# MiniRacer_V2.net
KiCad netlist of a schematic drawn in Altium Designer
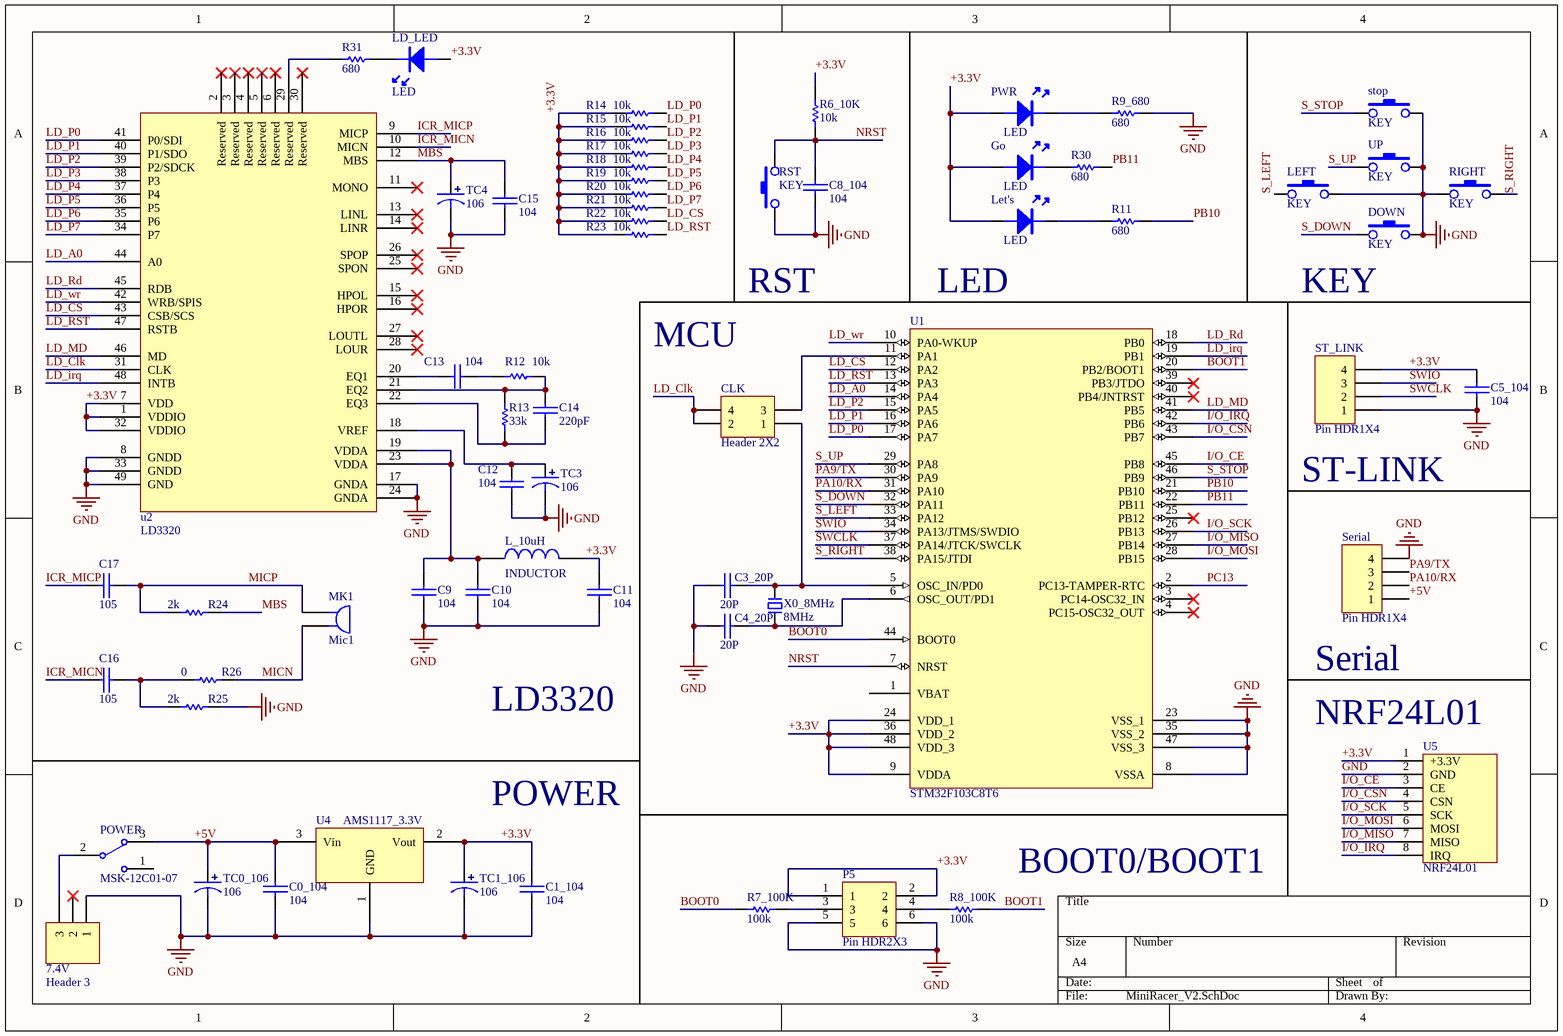
[diagram p0: MiniRacer_V2.SchDoc]

(export (version "E")
  (design (tool "Eeschema 10.0.6"))
  (components
    (comp (ref "7.4V")
      (value "Header 3")
      (footprint "HDR1X3")
      (description "Header, 3-Pin")
      (fields (field (name "PUBLISHER") "Altium Limited"))
      (libsource (lib "Miscellaneous Connectors") (part "Header 3"))
    )
    (comp (ref "C0_104")
      (value "104")
      (footprint "0603C")
      (description "无极性电容")
      (libsource (lib "电容") (part "CAP"))
    )
    (comp (ref "C1_104")
      (value "104")
      (footprint "0603C")
      (description "无极性电容")
      (libsource (lib "电容") (part "CAP"))
    )
    (comp (ref "C3_20P")
      (value "20P")
      (footprint "0603C")
      (description "无极性电容")
      (libsource (lib "电容") (part "CAP"))
    )
    (comp (ref "C4_20P")
      (value "20P")
      (footprint "0603C")
      (description "无极性电容")
      (libsource (lib "电容") (part "CAP"))
    )
    (comp (ref "C5_104")
      (value "104")
      (footprint "0603C")
      (description "无极性电容")
      (libsource (lib "电容") (part "CAP"))
    )
    (comp (ref "C8_104")
      (value "104")
      (footprint "0603C")
      (description "无极性电容")
      (libsource (lib "电容") (part "CAP"))
    )
    (comp (ref "C9")
      (value "104")
      (footprint "0603C")
      (description "无极性电容")
      (libsource (lib "电容") (part "CAP"))
    )
    (comp (ref "C10")
      (value "104")
      (footprint "0603C")
      (description "无极性电容")
      (libsource (lib "电容") (part "CAP"))
    )
    (comp (ref "C11")
      (value "104")
      (footprint "0603C")
      (description "无极性电容")
      (libsource (lib "电容") (part "CAP"))
    )
    (comp (ref "C12")
      (value "104")
      (footprint "0603C")
      (description "无极性电容")
      (libsource (lib "电容") (part "CAP"))
    )
    (comp (ref "C13")
      (value "104")
      (footprint "0603C")
      (description "无极性电容")
      (libsource (lib "电容") (part "CAP"))
    )
    (comp (ref "C14")
      (value "220pF")
      (footprint "0603C")
      (description "无极性电容")
      (libsource (lib "电容") (part "CAP"))
    )
    (comp (ref "C15")
      (value "104")
      (footprint "0603C")
      (description "无极性电容")
      (libsource (lib "电容") (part "CAP"))
    )
    (comp (ref "C16")
      (value "105")
      (footprint "0603C")
      (description "无极性电容")
      (libsource (lib "电容") (part "CAP"))
    )
    (comp (ref "C17")
      (value "105")
      (footprint "0603C")
      (description "无极性电容")
      (libsource (lib "电容") (part "CAP"))
    )
    (comp (ref "CLK")
      (value "Header 2X2")
      (footprint "HDR2X2")
      (description "Header, 2-Pin, Dual row")
      (fields (field (name "PUBLISHER") "Altium Limited"))
      (libsource (lib "Miscellaneous Connectors") (part "Header 2X2"))
    )
    (comp (ref "DOWN") (value "KEY") (footprint "DIP-3X6X4.3") (libsource (lib "轻触开关") (part "KEY")))
    (comp (ref "Go") (value "LED") (footprint "LED-0603Y") (libsource (lib "LED") (part "LED")))
    (comp (ref "LD_LED") (value "LED") (footprint "LED-0603Y") (libsource (lib "LED") (part "LED")))
    (comp (ref "LEFT") (value "KEY") (footprint "DIP-3X6X4.3") (libsource (lib "轻触开关") (part "KEY")))
    (comp (ref "Let's") (value "LED") (footprint "LED-0603Y") (libsource (lib "LED") (part "LED")))
    (comp (ref "L_10uH") (value "INDUCTOR") (footprint "0603L") (libsource (lib "电感") (part "INDUCTOR")))
    (comp (ref "MK1")
      (value "Mic1")
      (footprint "PIN2")
      (description "Microphone")
      (fields (field (name "PUBLISHER") "Altium Limited"))
      (libsource (lib "Miscellaneous Devices") (part "Mic1"))
    )
    (comp (ref "P5")
      (value "Pin HDR2X3")
      (footprint "Pin HDR2X3/2.54mm-S")
      (libsource (lib "排针") (part "Pin HDR2X3"))
    )
    (comp (ref "POWER")
      (value "MSK-12C01-07")
      (footprint "MSK-12C01-07")
      (libsource (lib "电源开关") (part "MSK-12C01-07"))
    )
    (comp (ref "PWR") (value "LED") (footprint "LED-0603Y") (libsource (lib "LED") (part "LED")))
    (comp (ref "R6_10K") (value "10k") (footprint "0603R") (libsource (lib "电阻") (part "RES")))
    (comp (ref "R7_100K") (value "100k") (footprint "0603R") (libsource (lib "电阻") (part "RES")))
    (comp (ref "R8_100K") (value "100k") (footprint "0603R") (libsource (lib "电阻") (part "RES")))
    (comp (ref "R9_680") (value "680") (footprint "0603R") (libsource (lib "电阻") (part "RES")))
    (comp (ref "R11") (value "680") (footprint "0603R") (libsource (lib "电阻") (part "RES")))
    (comp (ref "R12") (value "10k") (footprint "0603R") (libsource (lib "电阻") (part "RES")))
    (comp (ref "R13") (value "33k") (footprint "0603R") (libsource (lib "电阻") (part "RES")))
    (comp (ref "R14") (value "10k") (footprint "0603R") (libsource (lib "电阻") (part "RES")))
    (comp (ref "R15") (value "10k") (footprint "0603R") (libsource (lib "电阻") (part "RES")))
    (comp (ref "R16") (value "10k") (footprint "0603R") (libsource (lib "电阻") (part "RES")))
    (comp (ref "R17") (value "10k") (footprint "0603R") (libsource (lib "电阻") (part "RES")))
    (comp (ref "R18") (value "10k") (footprint "0603R") (libsource (lib "电阻") (part "RES")))
    (comp (ref "R19") (value "10k") (footprint "0603R") (libsource (lib "电阻") (part "RES")))
    (comp (ref "R20") (value "10k") (footprint "0603R") (libsource (lib "电阻") (part "RES")))
    (comp (ref "R21") (value "10k") (footprint "0603R") (libsource (lib "电阻") (part "RES")))
    (comp (ref "R22") (value "10k") (footprint "0603R") (libsource (lib "电阻") (part "RES")))
    (comp (ref "R23") (value "10k") (footprint "0603R") (libsource (lib "电阻") (part "RES")))
    (comp (ref "R24") (value "2k") (footprint "0603R") (libsource (lib "电阻") (part "RES")))
    (comp (ref "R25") (value "2k") (footprint "0603R") (libsource (lib "电阻") (part "RES")))
    (comp (ref "R26") (value "0") (footprint "0603R") (libsource (lib "电阻") (part "RES")))
    (comp (ref "R30") (value "680") (footprint "0603R") (libsource (lib "电阻") (part "RES")))
    (comp (ref "R31") (value "680") (footprint "0603R") (libsource (lib "电阻") (part "RES")))
    (comp (ref "RIGHT") (value "KEY") (footprint "DIP-3X6X4.3") (libsource (lib "轻触开关") (part "KEY")))
    (comp (ref "RST") (value "KEY") (footprint "SMD-3X6X2.5") (libsource (lib "轻触开关") (part "KEY")))
    (comp (ref "Serial")
      (value "Pin HDR1X4")
      (footprint "HDR1X4")
      (description "Header, 4-Pin")
      (fields (field (name "PUBLISHER") "Altium Limited"))
      (libsource (lib "Miscellaneous Connectors") (part "Header 4"))
    )
    (comp (ref "stop") (value "KEY") (footprint "DIP-3X6X4.3") (libsource (lib "轻触开关") (part "KEY")))
    (comp (ref "ST_LINK")
      (value "Pin HDR1X4")
      (footprint "HDR1X4")
      (description "Header, 4-Pin")
      (fields (field (name "PUBLISHER") "Altium Limited"))
      (libsource (lib "Miscellaneous Connectors") (part "Header 4"))
    )
    (comp (ref "TC0_106")
      (value "106")
      (footprint "TAJ-A/3216")
      (description "钽电容")
      (libsource (lib "电容") (part "TCAP"))
    )
    (comp (ref "TC1_106")
      (value "106")
      (footprint "TAJ-A/3216")
      (description "钽电容")
      (libsource (lib "电容") (part "TCAP"))
    )
    (comp (ref "TC3")
      (value "106")
      (footprint "TAJ-A/3216")
      (description "钽电容")
      (libsource (lib "电容") (part "TCAP"))
    )
    (comp (ref "TC4")
      (value "106")
      (footprint "TAJ-A/3216")
      (description "钽电容")
      (libsource (lib "电容") (part "TCAP"))
    )
    (comp (ref "U1")
      (value "STM32F103C8T6")
      (footprint "LQFP48 7X7")
      (libsource (lib "STM32系列") (part "STM32F103C8T6"))
    )
    (comp (ref "u2")
      (value "LD3320")
      (footprint "QFN50P700X700-48VAN")
      (libsource (lib "未分类IC") (part "LD3320"))
    )
    (comp (ref "U4")
      (value "AMS1117_3.3V")
      (footprint "SOT223")
      (description "三端稳压芯片")
      (libsource (lib "电源芯片") (part "AMS1117"))
    )
    (comp (ref "U5") (value "NRF24L01") (footprint "NRF24L01") (libsource (lib "未分类IC") (part "NRF24L01")))
    (comp (ref "UP") (value "KEY") (footprint "DIP-3X6X4.3") (libsource (lib "轻触开关") (part "KEY")))
    (comp (ref "X0_8MHz")
      (value "8MHz")
      (footprint "OSC 5032-2P")
      (description "2脚无源脚晶振")
      (libsource (lib "晶振") (part "XTAL-2P"))
    )
  )
  (nets
    (net (code "1") (name "/+3.3V") (class "Default")
      (node (ref "C11") (pin "1") (pinfunction "1_1") (pintype "passive"))
      (node (ref "C1_104") (pin "2") (pinfunction "2_2") (pintype "passive"))
      (node (ref "C5_104") (pin "1") (pinfunction "1_1") (pintype "passive"))
      (node (ref "Go") (pin "A") (pinfunction "A_A") (pintype "passive"))
      (node (ref "LD_LED") (pin "A") (pinfunction "A_A") (pintype "passive"))
      (node (ref "L_10uH") (pin "2") (pinfunction "2_2") (pintype "passive"))
      (node (ref "Let's") (pin "A") (pinfunction "A_A") (pintype "passive"))
      (node (ref "P5") (pin "1") (pinfunction "1_1") (pintype "passive"))
      (node (ref "P5") (pin "2") (pinfunction "2_2") (pintype "passive"))
      (node (ref "PWR") (pin "A") (pinfunction "A_A") (pintype "passive"))
      (node (ref "R14") (pin "1") (pinfunction "1_1") (pintype "passive"))
      (node (ref "R15") (pin "1") (pinfunction "1_1") (pintype "passive"))
      (node (ref "R16") (pin "1") (pinfunction "1_1") (pintype "passive"))
      (node (ref "R17") (pin "1") (pinfunction "1_1") (pintype "passive"))
      (node (ref "R18") (pin "1") (pinfunction "1_1") (pintype "passive"))
      (node (ref "R19") (pin "1") (pinfunction "1_1") (pintype "passive"))
      (node (ref "R20") (pin "1") (pinfunction "1_1") (pintype "passive"))
      (node (ref "R21") (pin "1") (pinfunction "1_1") (pintype "passive"))
      (node (ref "R22") (pin "1") (pinfunction "1_1") (pintype "passive"))
      (node (ref "R23") (pin "1") (pinfunction "1_1") (pintype "passive"))
      (node (ref "R6_10K") (pin "2") (pinfunction "2_2") (pintype "passive"))
      (node (ref "ST_LINK") (pin "4") (pinfunction "4_4") (pintype "passive"))
      (node (ref "TC1_106") (pin "1") (pinfunction "1_1") (pintype "passive"))
      (node (ref "U1") (pin "24") (pinfunction "VDD_1_24") (pintype "power_in"))
      (node (ref "U1") (pin "36") (pinfunction "VDD_2_36") (pintype "power_in"))
      (node (ref "U1") (pin "48") (pinfunction "VDD_3_48") (pintype "power_in"))
      (node (ref "U1") (pin "9") (pinfunction "VDDA_9") (pintype "power_in"))
      (node (ref "U4") (pin "2") (pinfunction "Vout_2") (pintype "passive"))
      (node (ref "U5") (pin "1") (pinfunction "+3.3V_1") (pintype "passive"))
      (node (ref "u2") (pin "1") (pinfunction "VDDIO_1") (pintype "passive"))
      (node (ref "u2") (pin "32") (pinfunction "VDDIO_32") (pintype "passive"))
      (node (ref "u2") (pin "7") (pinfunction "VDD_7") (pintype "passive"))
    )
    (net (code "2") (name "/+5V") (class "Default")
      (node (ref "C0_104") (pin "2") (pinfunction "2_2") (pintype "passive"))
      (node (ref "POWER") (pin "3") (pinfunction "3_3") (pintype "passive"))
      (node (ref "Serial") (pin "1") (pinfunction "1_1") (pintype "passive"))
      (node (ref "TC0_106") (pin "1") (pinfunction "1_1") (pintype "passive"))
      (node (ref "U4") (pin "3") (pinfunction "Vin_3") (pintype "passive"))
    )
    (net (code "3") (name "/BOOT0") (class "Default")
      (node (ref "R7_100K") (pin "2") (pinfunction "2_2") (pintype "passive"))
      (node (ref "U1") (pin "44") (pinfunction "BOOT0_44") (pintype "input"))
    )
    (net (code "4") (name "/BOOT1") (class "Default")
      (node (ref "R8_100K") (pin "1") (pinfunction "1_1") (pintype "passive"))
      (node (ref "U1") (pin "20") (pinfunction "PB2/BOOT1_20") (pintype "bidirectional"))
    )
    (net (code "5") (name "/ICR_MICN") (class "Default")
      (node (ref "C16") (pin "1") (pinfunction "1_1") (pintype "passive"))
      (node (ref "u2") (pin "10") (pinfunction "MICN_10") (pintype "passive"))
    )
    (net (code "6") (name "/ICR_MICP") (class "Default")
      (node (ref "C17") (pin "1") (pinfunction "1_1") (pintype "passive"))
      (node (ref "u2") (pin "9") (pinfunction "MICP_9") (pintype "passive"))
    )
    (net (code "7") (name "/I{slash}O_CE") (class "Default")
      (node (ref "U1") (pin "45") (pinfunction "PB8_45") (pintype "bidirectional"))
      (node (ref "U5") (pin "3") (pinfunction "CE_3") (pintype "passive"))
    )
    (net (code "8") (name "/I{slash}O_CSN") (class "Default")
      (node (ref "U1") (pin "43") (pinfunction "PB7_43") (pintype "bidirectional"))
      (node (ref "U5") (pin "4") (pinfunction "CSN_4") (pintype "passive"))
    )
    (net (code "9") (name "/I{slash}O_IRQ") (class "Default")
      (node (ref "U1") (pin "42") (pinfunction "PB6_42") (pintype "bidirectional"))
      (node (ref "U5") (pin "8") (pinfunction "IRQ_8") (pintype "passive"))
    )
    (net (code "10") (name "/I{slash}O_MISO") (class "Default")
      (node (ref "U1") (pin "27") (pinfunction "PB14_27") (pintype "bidirectional"))
      (node (ref "U5") (pin "7") (pinfunction "MISO_7") (pintype "passive"))
    )
    (net (code "11") (name "/I{slash}O_MOSI") (class "Default")
      (node (ref "U1") (pin "28") (pinfunction "PB15_28") (pintype "bidirectional"))
      (node (ref "U5") (pin "6") (pinfunction "MOSI_6") (pintype "passive"))
    )
    (net (code "12") (name "/I{slash}O_SCK") (class "Default")
      (node (ref "U1") (pin "26") (pinfunction "PB13_26") (pintype "bidirectional"))
      (node (ref "U5") (pin "5") (pinfunction "SCK_5") (pintype "passive"))
    )
    (net (code "13") (name "/LD_A0") (class "Default")
      (node (ref "U1") (pin "14") (pinfunction "PA4_14") (pintype "bidirectional"))
      (node (ref "u2") (pin "44") (pinfunction "A0_44") (pintype "passive"))
    )
    (net (code "14") (name "/LD_CS") (class "Default")
      (node (ref "R22") (pin "2") (pinfunction "2_2") (pintype "passive"))
      (node (ref "U1") (pin "12") (pinfunction "PA2_12") (pintype "bidirectional"))
      (node (ref "u2") (pin "43") (pinfunction "CSB/SCS_43") (pintype "passive"))
    )
    (net (code "15") (name "/LD_Clk") (class "Default")
      (node (ref "CLK") (pin "2") (pinfunction "2_2") (pintype "passive"))
      (node (ref "CLK") (pin "4") (pinfunction "4_4") (pintype "passive"))
      (node (ref "u2") (pin "31") (pinfunction "CLK_31") (pintype "passive"))
    )
    (net (code "16") (name "/LD_MD") (class "Default")
      (node (ref "U1") (pin "41") (pinfunction "PB5_41") (pintype "bidirectional"))
      (node (ref "u2") (pin "46") (pinfunction "MD_46") (pintype "passive"))
    )
    (net (code "17") (name "/LD_P0") (class "Default")
      (node (ref "R14") (pin "2") (pinfunction "2_2") (pintype "passive"))
      (node (ref "U1") (pin "17") (pinfunction "PA7_17") (pintype "bidirectional"))
      (node (ref "u2") (pin "41") (pinfunction "P0/SDI_41") (pintype "passive"))
    )
    (net (code "18") (name "/LD_P1") (class "Default")
      (node (ref "R15") (pin "2") (pinfunction "2_2") (pintype "passive"))
      (node (ref "U1") (pin "16") (pinfunction "PA6_16") (pintype "bidirectional"))
      (node (ref "u2") (pin "40") (pinfunction "P1/SDO_40") (pintype "passive"))
    )
    (net (code "19") (name "/LD_P2") (class "Default")
      (node (ref "R16") (pin "2") (pinfunction "2_2") (pintype "passive"))
      (node (ref "U1") (pin "15") (pinfunction "PA5_15") (pintype "bidirectional"))
      (node (ref "u2") (pin "39") (pinfunction "P2/SDCK_39") (pintype "passive"))
    )
    (net (code "20") (name "/LD_P3") (class "Default")
      (node (ref "R17") (pin "2") (pinfunction "2_2") (pintype "passive"))
      (node (ref "u2") (pin "38") (pinfunction "P3_38") (pintype "passive"))
    )
    (net (code "21") (name "/LD_P4") (class "Default")
      (node (ref "R18") (pin "2") (pinfunction "2_2") (pintype "passive"))
      (node (ref "u2") (pin "37") (pinfunction "P4_37") (pintype "passive"))
    )
    (net (code "22") (name "/LD_P5") (class "Default")
      (node (ref "R19") (pin "2") (pinfunction "2_2") (pintype "passive"))
      (node (ref "u2") (pin "36") (pinfunction "P5_36") (pintype "passive"))
    )
    (net (code "23") (name "/LD_P6") (class "Default")
      (node (ref "R20") (pin "2") (pinfunction "2_2") (pintype "passive"))
      (node (ref "u2") (pin "35") (pinfunction "P6_35") (pintype "passive"))
    )
    (net (code "24") (name "/LD_P7") (class "Default")
      (node (ref "R21") (pin "2") (pinfunction "2_2") (pintype "passive"))
      (node (ref "u2") (pin "34") (pinfunction "P7_34") (pintype "passive"))
    )
    (net (code "25") (name "/LD_RST") (class "Default")
      (node (ref "R23") (pin "2") (pinfunction "2_2") (pintype "passive"))
      (node (ref "U1") (pin "13") (pinfunction "PA3_13") (pintype "bidirectional"))
      (node (ref "u2") (pin "47") (pinfunction "RSTB_47") (pintype "passive"))
    )
    (net (code "26") (name "/LD_Rd") (class "Default")
      (node (ref "U1") (pin "18") (pinfunction "PB0_18") (pintype "bidirectional"))
      (node (ref "u2") (pin "45") (pinfunction "RDB_45") (pintype "passive"))
    )
    (net (code "27") (name "/LD_irq") (class "Default")
      (node (ref "U1") (pin "19") (pinfunction "PB1_19") (pintype "bidirectional"))
      (node (ref "u2") (pin "48") (pinfunction "INTB_48") (pintype "passive"))
    )
    (net (code "28") (name "/LD_wr") (class "Default")
      (node (ref "U1") (pin "10") (pinfunction "PA0-WKUP_10") (pintype "bidirectional"))
      (node (ref "u2") (pin "42") (pinfunction "WRB/SPIS_42") (pintype "passive"))
    )
    (net (code "29") (name "/MBS") (class "Default")
      (node (ref "C15") (pin "1") (pinfunction "1_1") (pintype "passive"))
      (node (ref "R24") (pin "2") (pinfunction "2_2") (pintype "passive"))
      (node (ref "TC4") (pin "1") (pinfunction "1_1") (pintype "passive"))
      (node (ref "u2") (pin "12") (pinfunction "MBS_12") (pintype "passive"))
    )
    (net (code "30") (name "/MICN") (class "Default")
      (node (ref "MK1") (pin "2") (pinfunction "2_2") (pintype "passive"))
      (node (ref "R26") (pin "2") (pinfunction "2_2") (pintype "passive"))
    )
    (net (code "31") (name "/MICP") (class "Default")
      (node (ref "C17") (pin "2") (pinfunction "2_2") (pintype "passive"))
      (node (ref "MK1") (pin "1") (pinfunction "1_1") (pintype "passive"))
      (node (ref "R24") (pin "1") (pinfunction "1_1") (pintype "passive"))
    )
    (net (code "32") (name "/NRST") (class "Default")
      (node (ref "C8_104") (pin "1") (pinfunction "1_1") (pintype "passive"))
      (node (ref "R6_10K") (pin "1") (pinfunction "1_1") (pintype "passive"))
      (node (ref "RST") (pin "3") (pinfunction "3_3") (pintype "passive"))
      (node (ref "U1") (pin "7") (pinfunction "NRST_7") (pintype "bidirectional"))
    )
    (net (code "33") (name "/PA9{slash}TX") (class "Default")
      (node (ref "Serial") (pin "3") (pinfunction "3_3") (pintype "passive"))
      (node (ref "U1") (pin "30") (pinfunction "PA9_30") (pintype "bidirectional"))
    )
    (net (code "34") (name "/PA10{slash}RX") (class "Default")
      (node (ref "Serial") (pin "2") (pinfunction "2_2") (pintype "passive"))
      (node (ref "U1") (pin "31") (pinfunction "PA10_31") (pintype "bidirectional"))
    )
    (net (code "35") (name "/PB10") (class "Default")
      (node (ref "R11") (pin "1") (pinfunction "1_1") (pintype "passive"))
      (node (ref "U1") (pin "21") (pinfunction "PB10_21") (pintype "bidirectional"))
    )
    (net (code "36") (name "/PB11") (class "Default")
      (node (ref "R30") (pin "1") (pinfunction "1_1") (pintype "passive"))
      (node (ref "U1") (pin "22") (pinfunction "PB11_22") (pintype "bidirectional"))
    )
    (net (code "37") (name "/PC13") (class "Default")
      (node (ref "U1") (pin "2") (pinfunction "PC13-TAMPER-RTC_2") (pintype "bidirectional"))
    )
    (net (code "38") (name "/SWCLK") (class "Default")
      (node (ref "ST_LINK") (pin "2") (pinfunction "2_2") (pintype "passive"))
      (node (ref "U1") (pin "37") (pinfunction "PA14/JTCK/SWCLK_37") (pintype "bidirectional"))
    )
    (net (code "39") (name "/SWIO") (class "Default")
      (node (ref "ST_LINK") (pin "3") (pinfunction "3_3") (pintype "passive"))
      (node (ref "U1") (pin "34") (pinfunction "PA13/JTMS/SWDIO_34") (pintype "bidirectional"))
    )
    (net (code "40") (name "/S_DOWN") (class "Default")
      (node (ref "DOWN") (pin "1") (pinfunction "1_1") (pintype "passive"))
      (node (ref "U1") (pin "32") (pinfunction "PA11_32") (pintype "bidirectional"))
    )
    (net (code "41") (name "/S_LEFT") (class "Default")
      (node (ref "LEFT") (pin "1") (pinfunction "1_1") (pintype "passive"))
      (node (ref "U1") (pin "33") (pinfunction "PA12_33") (pintype "bidirectional"))
    )
    (net (code "42") (name "/S_RIGHT") (class "Default")
      (node (ref "RIGHT") (pin "3") (pinfunction "3_3") (pintype "passive"))
      (node (ref "U1") (pin "38") (pinfunction "PA15/JTDI_38") (pintype "bidirectional"))
    )
    (net (code "43") (name "/S_STOP") (class "Default")
      (node (ref "U1") (pin "46") (pinfunction "PB9_46") (pintype "bidirectional"))
      (node (ref "stop") (pin "1") (pinfunction "1_1") (pintype "passive"))
    )
    (net (code "44") (name "/S_UP") (class "Default")
      (node (ref "U1") (pin "29") (pinfunction "PA8_29") (pintype "bidirectional"))
      (node (ref "UP") (pin "1") (pinfunction "1_1") (pintype "passive"))
    )
    (net (code "45") (name "GND") (class "Default")
      (node (ref "7.4V") (pin "1") (pinfunction "1_1") (pintype "passive"))
      (node (ref "C0_104") (pin "1") (pinfunction "1_1") (pintype "passive"))
      (node (ref "C10") (pin "2") (pinfunction "2_2") (pintype "passive"))
      (node (ref "C11") (pin "2") (pinfunction "2_2") (pintype "passive"))
      (node (ref "C12") (pin "2") (pinfunction "2_2") (pintype "passive"))
      (node (ref "C15") (pin "2") (pinfunction "2_2") (pintype "passive"))
      (node (ref "C1_104") (pin "1") (pinfunction "1_1") (pintype "passive"))
      (node (ref "C3_20P") (pin "2") (pinfunction "2_2") (pintype "passive"))
      (node (ref "C4_20P") (pin "2") (pinfunction "2_2") (pintype "passive"))
      (node (ref "C5_104") (pin "2") (pinfunction "2_2") (pintype "passive"))
      (node (ref "C8_104") (pin "2") (pinfunction "2_2") (pintype "passive"))
      (node (ref "C9") (pin "2") (pinfunction "2_2") (pintype "passive"))
      (node (ref "DOWN") (pin "3") (pinfunction "3_3") (pintype "passive"))
      (node (ref "LEFT") (pin "3") (pinfunction "3_3") (pintype "passive"))
      (node (ref "P5") (pin "5") (pinfunction "5_5") (pintype "passive"))
      (node (ref "P5") (pin "6") (pinfunction "6_6") (pintype "passive"))
      (node (ref "R25") (pin "2") (pinfunction "2_2") (pintype "passive"))
      (node (ref "R9_680") (pin "1") (pinfunction "1_1") (pintype "passive"))
      (node (ref "RIGHT") (pin "1") (pinfunction "1_1") (pintype "passive"))
      (node (ref "RST") (pin "1") (pinfunction "1_1") (pintype "passive"))
      (node (ref "ST_LINK") (pin "1") (pinfunction "1_1") (pintype "passive"))
      (node (ref "Serial") (pin "4") (pinfunction "4_4") (pintype "passive"))
      (node (ref "TC0_106") (pin "2") (pinfunction "2_2") (pintype "passive"))
      (node (ref "TC1_106") (pin "2") (pinfunction "2_2") (pintype "passive"))
      (node (ref "TC3") (pin "2") (pinfunction "2_2") (pintype "passive"))
      (node (ref "TC4") (pin "2") (pinfunction "2_2") (pintype "passive"))
      (node (ref "U1") (pin "23") (pinfunction "VSS_1_23") (pintype "power_in"))
      (node (ref "U1") (pin "35") (pinfunction "VSS_2_35") (pintype "power_in"))
      (node (ref "U1") (pin "47") (pinfunction "VSS_3_47") (pintype "power_in"))
      (node (ref "U1") (pin "8") (pinfunction "VSSA_8") (pintype "power_in"))
      (node (ref "U4") (pin "1") (pinfunction "GND_1") (pintype "passive"))
      (node (ref "U5") (pin "2") (pinfunction "GND_2") (pintype "passive"))
      (node (ref "UP") (pin "3") (pinfunction "3_3") (pintype "passive"))
      (node (ref "stop") (pin "3") (pinfunction "3_3") (pintype "passive"))
      (node (ref "u2") (pin "17") (pinfunction "GNDA_17") (pintype "passive"))
      (node (ref "u2") (pin "24") (pinfunction "GNDA_24") (pintype "passive"))
      (node (ref "u2") (pin "33") (pinfunction "GNDD_33") (pintype "passive"))
      (node (ref "u2") (pin "49") (pinfunction "GND_49") (pintype "passive"))
      (node (ref "u2") (pin "8") (pinfunction "GNDD_8") (pintype "passive"))
    )
    (net (code "46") (name "Net-(7.4V-Pad3)") (class "Default")
      (node (ref "7.4V") (pin "3") (pinfunction "3_3") (pintype "passive"))
      (node (ref "POWER") (pin "2") (pinfunction "2_2") (pintype "passive"))
    )
    (net (code "47") (name "Net-(C10-Pad1)") (class "Default")
      (node (ref "C10") (pin "1") (pinfunction "1_1") (pintype "passive"))
      (node (ref "C9") (pin "1") (pinfunction "1_1") (pintype "passive"))
      (node (ref "L_10uH") (pin "1") (pinfunction "1_1") (pintype "passive"))
      (node (ref "u2") (pin "19") (pinfunction "VDDA_19") (pintype "passive"))
      (node (ref "u2") (pin "23") (pinfunction "VDDA_23") (pintype "passive"))
    )
    (net (code "48") (name "Net-(C13-Pad2)") (class "Default")
      (node (ref "C13") (pin "2") (pinfunction "2_2") (pintype "passive"))
      (node (ref "R12") (pin "2") (pinfunction "2_2") (pintype "passive"))
    )
    (net (code "49") (name "Net-(C16-Pad2)") (class "Default")
      (node (ref "C16") (pin "2") (pinfunction "2_2") (pintype "passive"))
      (node (ref "R25") (pin "1") (pinfunction "1_1") (pintype "passive"))
      (node (ref "R26") (pin "1") (pinfunction "1_1") (pintype "passive"))
    )
    (net (code "50") (name "Net-(Go-PadK)") (class "Default")
      (node (ref "Go") (pin "K") (pinfunction "K_K") (pintype "passive"))
      (node (ref "R30") (pin "2") (pinfunction "2_2") (pintype "passive"))
    )
    (net (code "51") (name "Net-(LD_LED-PadK)") (class "Default")
      (node (ref "LD_LED") (pin "K") (pinfunction "K_K") (pintype "passive"))
      (node (ref "R31") (pin "2") (pinfunction "2_2") (pintype "passive"))
    )
    (net (code "52") (name "Net-(Let's-PadK)") (class "Default")
      (node (ref "Let's") (pin "K") (pinfunction "K_K") (pintype "passive"))
      (node (ref "R11") (pin "2") (pinfunction "2_2") (pintype "passive"))
    )
    (net (code "53") (name "Net-(P5-Pad3)") (class "Default")
      (node (ref "P5") (pin "3") (pinfunction "3_3") (pintype "passive"))
      (node (ref "R7_100K") (pin "1") (pinfunction "1_1") (pintype "passive"))
    )
    (net (code "54") (name "Net-(P5-Pad4)") (class "Default")
      (node (ref "P5") (pin "4") (pinfunction "4_4") (pintype "passive"))
      (node (ref "R8_100K") (pin "2") (pinfunction "2_2") (pintype "passive"))
    )
    (net (code "55") (name "Net-(PWR-PadK)") (class "Default")
      (node (ref "PWR") (pin "K") (pinfunction "K_K") (pintype "passive"))
      (node (ref "R9_680") (pin "2") (pinfunction "2_2") (pintype "passive"))
    )
    (net (code "56") (name "Net-(R31-Pad1)") (class "Default")
      (node (ref "R31") (pin "1") (pinfunction "1_1") (pintype "passive"))
      (node (ref "u2") (pin "29") (pinfunction "Reserved_29") (pintype "passive"))
    )
    (net (code "57") (name "Net-(U1-OSC_IN{slash}PD0)") (class "Default")
      (node (ref "C3_20P") (pin "1") (pinfunction "1_1") (pintype "passive"))
      (node (ref "CLK") (pin "1") (pinfunction "1_1") (pintype "passive"))
      (node (ref "U1") (pin "5") (pinfunction "OSC_IN/PD0_5") (pintype "input"))
      (node (ref "X0_8MHz") (pin "2") (pinfunction "2_2") (pintype "passive"))
    )
    (net (code "58") (name "Net-(U1-OSC_OUT{slash}PD1)") (class "Default")
      (node (ref "C4_20P") (pin "1") (pinfunction "1_1") (pintype "passive"))
      (node (ref "U1") (pin "6") (pinfunction "OSC_OUT/PD1_6") (pintype "output"))
      (node (ref "X0_8MHz") (pin "1") (pinfunction "1_1") (pintype "passive"))
    )
    (net (code "59") (name "Net-(U1-PA1)") (class "Default")
      (node (ref "CLK") (pin "3") (pinfunction "3_3") (pintype "passive"))
      (node (ref "U1") (pin "11") (pinfunction "PA1_11") (pintype "bidirectional"))
    )
    (net (code "60") (name "Net-(u2-EQ1)") (class "Default")
      (node (ref "C13") (pin "1") (pinfunction "1_1") (pintype "passive"))
      (node (ref "u2") (pin "20") (pinfunction "EQ1_20") (pintype "passive"))
    )
    (net (code "61") (name "Net-(u2-EQ2)") (class "Default")
      (node (ref "C14") (pin "1") (pinfunction "1_1") (pintype "passive"))
      (node (ref "R12") (pin "1") (pinfunction "1_1") (pintype "passive"))
      (node (ref "R13") (pin "1") (pinfunction "1_1") (pintype "passive"))
      (node (ref "u2") (pin "21") (pinfunction "EQ2_21") (pintype "passive"))
    )
    (net (code "62") (name "Net-(u2-EQ3)") (class "Default")
      (node (ref "C14") (pin "2") (pinfunction "2_2") (pintype "passive"))
      (node (ref "R13") (pin "2") (pinfunction "2_2") (pintype "passive"))
      (node (ref "u2") (pin "22") (pinfunction "EQ3_22") (pintype "passive"))
    )
    (net (code "63") (name "Net-(u2-VREF)") (class "Default")
      (node (ref "C12") (pin "1") (pinfunction "1_1") (pintype "passive"))
      (node (ref "TC3") (pin "1") (pinfunction "1_1") (pintype "passive"))
      (node (ref "u2") (pin "18") (pinfunction "VREF_18") (pintype "passive"))
    )
    (net (code "64") (name "unconnected-(7.4V-Pad2)") (class "Default")
      (node (ref "7.4V") (pin "2") (pinfunction "2_2") (pintype "passive+no_connect"))
    )
    (net (code "65") (name "unconnected-(POWER-Pad1)") (class "Default")
      (node (ref "POWER") (pin "1") (pinfunction "1_1") (pintype "passive"))
    )
    (net (code "66") (name "unconnected-(U1-PB3{slash}JTDO-Pad39)") (class "Default")
      (node (ref "U1") (pin "39") (pinfunction "PB3/JTDO_39") (pintype "bidirectional+no_connect"))
    )
    (net (code "67") (name "unconnected-(U1-PB4{slash}JNTRST-Pad40)") (class "Default")
      (node (ref "U1") (pin "40") (pinfunction "PB4/JNTRST_40") (pintype "bidirectional+no_connect"))
    )
    (net (code "68") (name "unconnected-(U1-PB12-Pad25)") (class "Default")
      (node (ref "U1") (pin "25") (pinfunction "PB12_25") (pintype "bidirectional+no_connect"))
    )
    (net (code "69") (name "unconnected-(U1-PC14-OSC32_IN-Pad3)") (class "Default")
      (node (ref "U1") (pin "3") (pinfunction "PC14-OSC32_IN_3") (pintype "bidirectional+no_connect"))
    )
    (net (code "70") (name "unconnected-(U1-PC15-OSC32_OUT-Pad4)") (class "Default")
      (node (ref "U1") (pin "4") (pinfunction "PC15-OSC32_OUT_4") (pintype "bidirectional+no_connect"))
    )
    (net (code "71") (name "unconnected-(U1-VBAT-Pad1)") (class "Default")
      (node (ref "U1") (pin "1") (pinfunction "VBAT_1") (pintype "power_in"))
    )
    (net (code "72") (name "unconnected-(u2-HPOL-Pad15)") (class "Default")
      (node (ref "u2") (pin "15") (pinfunction "HPOL_15") (pintype "passive+no_connect"))
    )
    (net (code "73") (name "unconnected-(u2-HPOR-Pad16)") (class "Default")
      (node (ref "u2") (pin "16") (pinfunction "HPOR_16") (pintype "passive+no_connect"))
    )
    (net (code "74") (name "unconnected-(u2-LINL-Pad13)") (class "Default")
      (node (ref "u2") (pin "13") (pinfunction "LINL_13") (pintype "passive+no_connect"))
    )
    (net (code "75") (name "unconnected-(u2-LINR-Pad14)") (class "Default")
      (node (ref "u2") (pin "14") (pinfunction "LINR_14") (pintype "passive+no_connect"))
    )
    (net (code "76") (name "unconnected-(u2-LOUR-Pad28)") (class "Default")
      (node (ref "u2") (pin "28") (pinfunction "LOUR_28") (pintype "passive+no_connect"))
    )
    (net (code "77") (name "unconnected-(u2-LOUTL-Pad27)") (class "Default")
      (node (ref "u2") (pin "27") (pinfunction "LOUTL_27") (pintype "passive+no_connect"))
    )
    (net (code "78") (name "unconnected-(u2-MONO-Pad11)") (class "Default")
      (node (ref "u2") (pin "11") (pinfunction "MONO_11") (pintype "passive+no_connect"))
    )
    (net (code "79") (name "unconnected-(u2-Reserved-Pad2)") (class "Default")
      (node (ref "u2") (pin "2") (pinfunction "Reserved_2") (pintype "passive+no_connect"))
    )
    (net (code "80") (name "unconnected-(u2-Reserved-Pad3)") (class "Default")
      (node (ref "u2") (pin "3") (pinfunction "Reserved_3") (pintype "passive+no_connect"))
    )
    (net (code "81") (name "unconnected-(u2-Reserved-Pad4)") (class "Default")
      (node (ref "u2") (pin "4") (pinfunction "Reserved_4") (pintype "passive+no_connect"))
    )
    (net (code "82") (name "unconnected-(u2-Reserved-Pad5)") (class "Default")
      (node (ref "u2") (pin "5") (pinfunction "Reserved_5") (pintype "passive+no_connect"))
    )
    (net (code "83") (name "unconnected-(u2-Reserved-Pad6)") (class "Default")
      (node (ref "u2") (pin "6") (pinfunction "Reserved_6") (pintype "passive+no_connect"))
    )
    (net (code "84") (name "unconnected-(u2-Reserved-Pad30)") (class "Default")
      (node (ref "u2") (pin "30") (pinfunction "Reserved_30") (pintype "passive+no_connect"))
    )
    (net (code "85") (name "unconnected-(u2-SPON-Pad25)") (class "Default")
      (node (ref "u2") (pin "25") (pinfunction "SPON_25") (pintype "passive+no_connect"))
    )
    (net (code "86") (name "unconnected-(u2-SPOP-Pad26)") (class "Default")
      (node (ref "u2") (pin "26") (pinfunction "SPOP_26") (pintype "passive+no_connect"))
    )
  )
)
